# 1_interface.net
KiCad netlist of a schematic drawn in Altium Designer
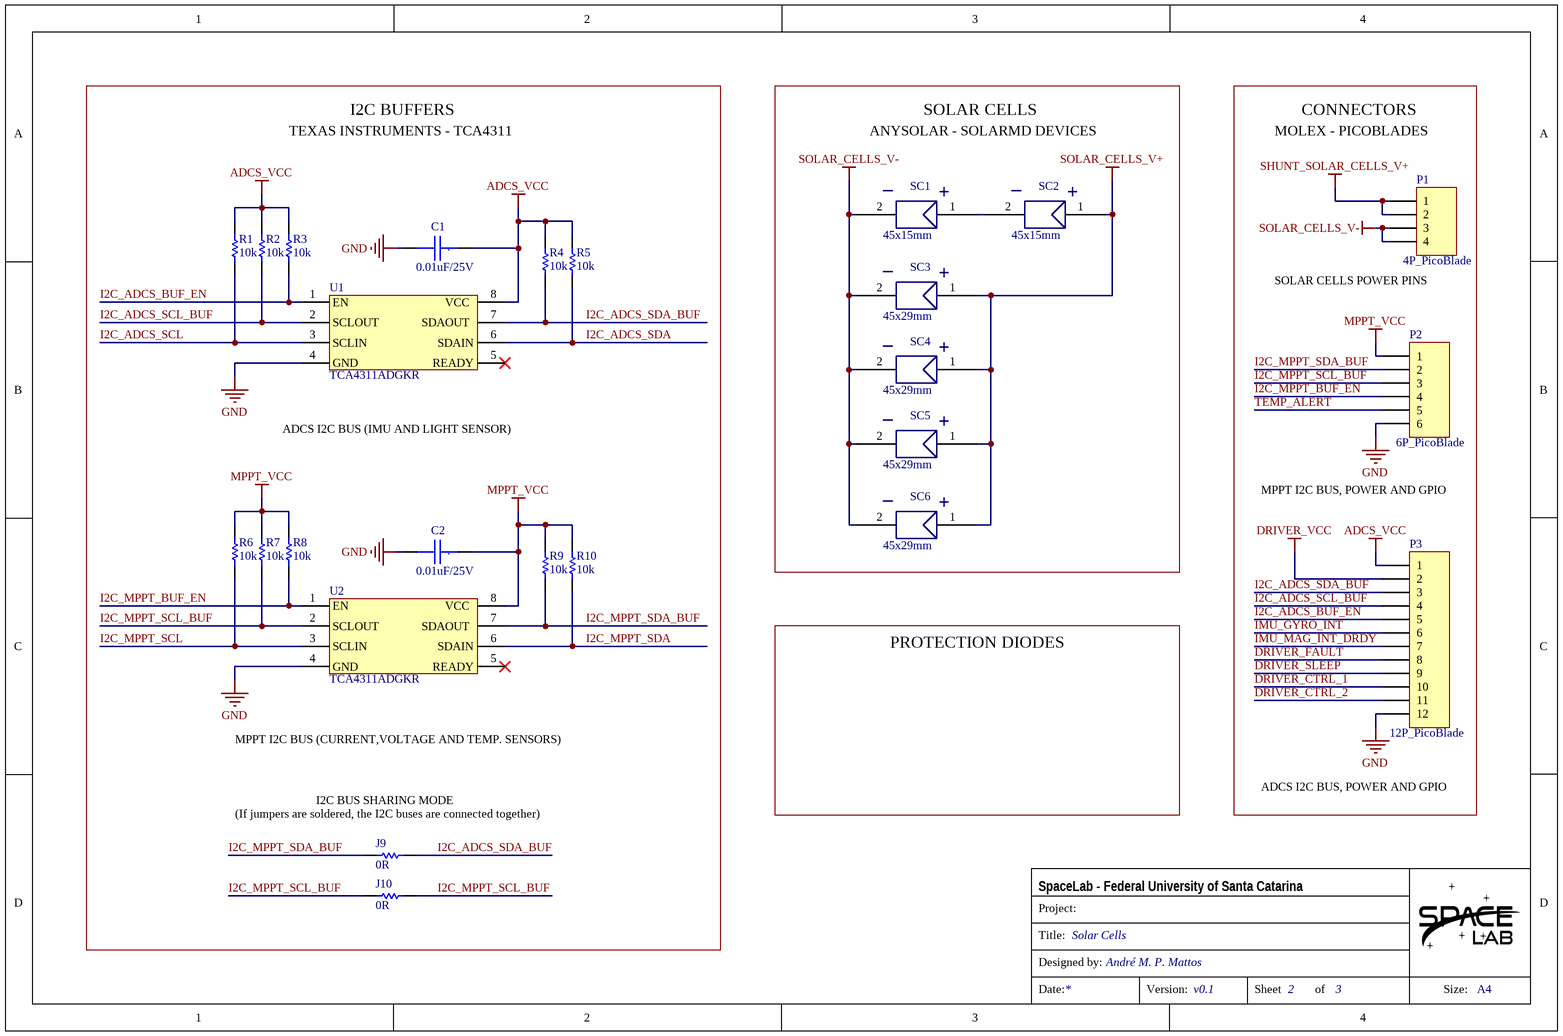
[diagram p0: 1_interface.schdoc]

(export (version "E")
  (design (tool "Eeschema 10.0.6"))
  (components
    (comp (ref "C1")
      (value "0.01uF/25V")
      (footprint "CC0805")
      (description "CAP CER 0.01uF 25V 10% X7R 0805")
      (fields (field (name "PARTNUMBER") "CL21B103KAANNNC"))
      (libsource (lib "schematics_library_legacy") (part "Cap_Cer_X7R_0.01uF_50V_0805"))
    )
    (comp (ref "C2")
      (value "0.01uF/25V")
      (footprint "CC0805")
      (description "CAP CER 0.01uF 25V 10% X7R 0805")
      (fields (field (name "PARTNUMBER") "CL21B103KAANNNC"))
      (libsource (lib "schematics_library_legacy") (part "Cap_Cer_X7R_0.01uF_50V_0805"))
    )
    (comp (ref "J9")
      (value "0R")
      (footprint "0805")
      (description "RES 0R OHM 1/16W JUMPER 0805")
      (fields (field (name "PARTNUMBER") "CRCW08050000Z0EA"))
      (libsource (lib "schematics_library_legacy") (part "R0R_JUMPER_1/16W_0805"))
    )
    (comp (ref "J10")
      (value "0R")
      (footprint "0805")
      (description "RES 0R OHM 1/16W JUMPER 0805")
      (fields (field (name "PARTNUMBER") "CRCW08050000Z0EA"))
      (libsource (lib "schematics_library_legacy") (part "R0R_JUMPER_1/16W_0805"))
    )
    (comp (ref "P1")
      (value "4P_PicoBlade")
      (footprint "HDR4 PicoBlade")
      (description "Header, 4-Pin")
      (fields
        (field (name "PARTNUMBER") "53398-0471")
        (field (name "MANUFACTURER") "Molex")
        (field (name "PUBLISHER") "Altium Limited")
      )
      (libsource (lib "schematics_library_legacy") (part "Header 4_PicoBlade"))
    )
    (comp (ref "P2")
      (value "6P_PicoBlade")
      (footprint "HDR6 PicoBlade")
      (description "Header, 6-Pin, Right Angle")
      (fields (field (name "PARTNUMBER") "53398-0671") (field (name "PUBLISHER") "Altium Limited"))
      (libsource (lib "schematics_library_legacy") (part "Header 6H_PicoBlade"))
    )
    (comp (ref "P3")
      (value "12P_PicoBlade")
      (footprint "HDR12 PicoBlade - duplicate")
      (description "Header, 12-Pin")
      (fields (field (name "PARTNUMBER") "53398-1271") (field (name "PUBLISHER") "Altium Limited"))
      (libsource (lib "schematics_library_legacy") (part "Header 12_PicoBlade"))
    )
    (comp (ref "R1")
      (value "10k")
      (footprint "0805")
      (description "RES 10K OHM 1/8W 1%  0805")
      (fields (field (name "PARTNUMBER") "CRCW080510K0FKEA"))
      (libsource (lib "schematics_library_legacy") (part "R10k_1%_1/8W_0805"))
    )
    (comp (ref "R2")
      (value "10k")
      (footprint "0805")
      (description "RES 10K OHM 1/8W 1%  0805")
      (fields (field (name "PARTNUMBER") "CRCW080510K0FKEA"))
      (libsource (lib "schematics_library_legacy") (part "R10k_1%_1/8W_0805"))
    )
    (comp (ref "R3")
      (value "10k")
      (footprint "0805")
      (description "RES 10K OHM 1/8W 1%  0805")
      (fields (field (name "PARTNUMBER") "CRCW080510K0FKEA"))
      (libsource (lib "schematics_library_legacy") (part "R10k_1%_1/8W_0805"))
    )
    (comp (ref "R4")
      (value "10k")
      (footprint "0805")
      (description "RES 10K OHM 1/8W 1%  0805")
      (fields (field (name "PARTNUMBER") "CRCW080510K0FKEA"))
      (libsource (lib "schematics_library_legacy") (part "R10k_1%_1/8W_0805"))
    )
    (comp (ref "R5")
      (value "10k")
      (footprint "0805")
      (description "RES 10K OHM 1/8W 1%  0805")
      (fields (field (name "PARTNUMBER") "CRCW080510K0FKEA"))
      (libsource (lib "schematics_library_legacy") (part "R10k_1%_1/8W_0805"))
    )
    (comp (ref "R6")
      (value "10k")
      (footprint "0805")
      (description "RES 10K OHM 1/8W 1%  0805")
      (fields (field (name "PARTNUMBER") "CRCW080510K0FKEA"))
      (libsource (lib "schematics_library_legacy") (part "R10k_1%_1/8W_0805"))
    )
    (comp (ref "R7")
      (value "10k")
      (footprint "0805")
      (description "RES 10K OHM 1/8W 1%  0805")
      (fields (field (name "PARTNUMBER") "CRCW080510K0FKEA"))
      (libsource (lib "schematics_library_legacy") (part "R10k_1%_1/8W_0805"))
    )
    (comp (ref "R8")
      (value "10k")
      (footprint "0805")
      (description "RES 10K OHM 1/8W 1%  0805")
      (fields (field (name "PARTNUMBER") "CRCW080510K0FKEA"))
      (libsource (lib "schematics_library_legacy") (part "R10k_1%_1/8W_0805"))
    )
    (comp (ref "R9")
      (value "10k")
      (footprint "0805")
      (description "RES 10K OHM 1/8W 1%  0805")
      (fields (field (name "PARTNUMBER") "CRCW080510K0FKEA"))
      (libsource (lib "schematics_library_legacy") (part "R10k_1%_1/8W_0805"))
    )
    (comp (ref "R10")
      (value "10k")
      (footprint "0805")
      (description "RES 10K OHM 1/8W 1%  0805")
      (fields (field (name "PARTNUMBER") "CRCW080510K0FKEA"))
      (libsource (lib "schematics_library_legacy") (part "R10k_1%_1/8W_0805"))
    )
    (comp (ref "SC1")
      (value "SC")
      (footprint "45x15mm_cell")
      (description "sm141k04lv")
      (fields (field (name "SIZE") "45x15mm"))
      (libsource (lib "schematics_library_legacy") (part "solar_cell_sm141k04lv"))
    )
    (comp (ref "SC2")
      (value "SC")
      (footprint "45x15mm_cell")
      (description "sm141k04lv")
      (fields (field (name "SIZE") "45x15mm"))
      (libsource (lib "schematics_library_legacy") (part "solar_cell_sm141k04lv"))
    )
    (comp (ref "SC3")
      (value "SC")
      (footprint "45x29mm_cell")
      (description "sm141k08lv")
      (fields (field (name "SIZE") "45x29mm"))
      (libsource (lib "schematics_library_legacy") (part "solar_cell_sm141k08lv"))
    )
    (comp (ref "SC4")
      (value "SC")
      (footprint "45x29mm_cell")
      (description "sm141k08lv")
      (fields (field (name "SIZE") "45x29mm"))
      (libsource (lib "schematics_library_legacy") (part "solar_cell_sm141k08lv"))
    )
    (comp (ref "SC5")
      (value "SC")
      (footprint "45x29mm_cell")
      (description "sm141k08lv")
      (fields (field (name "SIZE") "45x29mm"))
      (libsource (lib "schematics_library_legacy") (part "solar_cell_sm141k08lv"))
    )
    (comp (ref "SC6")
      (value "SC")
      (footprint "45x29mm_cell")
      (description "sm141k08lv")
      (fields (field (name "SIZE") "45x29mm"))
      (libsource (lib "schematics_library_legacy") (part "solar_cell_sm141k08lv"))
    )
    (comp (ref "U1")
      (value "TCA4311ADGKR")
      (footprint "DGK8")
      (description "IC SIGNAL BUFFER I2C VSSOP-8")
      (libsource (lib "schematics_library_legacy") (part "TCA4311ADGKR"))
    )
    (comp (ref "U2")
      (value "TCA4311ADGKR")
      (footprint "DGK8")
      (description "IC SIGNAL BUFFER I2C VSSOP-8")
      (libsource (lib "schematics_library_legacy") (part "TCA4311ADGKR"))
    )
  )
  (nets
    (net (code "1") (name "/DRIVER_CTRL_1") (class "Default")
      (node (ref "P3") (pin "10") (pinfunction "10_10") (pintype "passive"))
    )
    (net (code "2") (name "/DRIVER_CTRL_2") (class "Default")
      (node (ref "P3") (pin "11") (pinfunction "11_11") (pintype "passive"))
    )
    (net (code "3") (name "/DRIVER_FAULT") (class "Default")
      (node (ref "P3") (pin "8") (pinfunction "8_8") (pintype "passive"))
    )
    (net (code "4") (name "/DRIVER_SLEEP") (class "Default")
      (node (ref "P3") (pin "9") (pinfunction "9_9") (pintype "passive"))
    )
    (net (code "5") (name "/I2C_ADCS_BUF_EN") (class "Default")
      (node (ref "P3") (pin "5") (pinfunction "5_5") (pintype "passive"))
      (node (ref "R3") (pin "1") (pinfunction "1_1") (pintype "passive"))
      (node (ref "U1") (pin "1") (pinfunction "EN_1") (pintype "passive"))
    )
    (net (code "6") (name "/I2C_ADCS_SCL") (class "Default")
      (node (ref "R1") (pin "1") (pinfunction "1_1") (pintype "passive"))
      (node (ref "U1") (pin "3") (pinfunction "SCLIN_3") (pintype "passive"))
    )
    (net (code "7") (name "/I2C_ADCS_SCL_BUF") (class "Default")
      (node (ref "P3") (pin "4") (pinfunction "4_4") (pintype "passive"))
      (node (ref "R2") (pin "1") (pinfunction "1_1") (pintype "passive"))
      (node (ref "U1") (pin "2") (pinfunction "SCLOUT_2") (pintype "passive"))
    )
    (net (code "8") (name "/I2C_ADCS_SDA") (class "Default")
      (node (ref "R5") (pin "1") (pinfunction "1_1") (pintype "passive"))
      (node (ref "U1") (pin "6") (pinfunction "SDAIN_6") (pintype "passive"))
    )
    (net (code "9") (name "/I2C_ADCS_SDA_BUF") (class "Default")
      (node (ref "J9") (pin "1") (pinfunction "1_1") (pintype "passive"))
      (node (ref "P3") (pin "3") (pinfunction "3_3") (pintype "passive"))
      (node (ref "R4") (pin "1") (pinfunction "1_1") (pintype "passive"))
      (node (ref "U1") (pin "7") (pinfunction "SDAOUT_7") (pintype "passive"))
    )
    (net (code "10") (name "/I2C_MPPT_BUF_EN") (class "Default")
      (node (ref "P2") (pin "4") (pinfunction "4_4") (pintype "passive"))
      (node (ref "R8") (pin "1") (pinfunction "1_1") (pintype "passive"))
      (node (ref "U2") (pin "1") (pinfunction "EN_1") (pintype "passive"))
    )
    (net (code "11") (name "/I2C_MPPT_SCL") (class "Default")
      (node (ref "R6") (pin "1") (pinfunction "1_1") (pintype "passive"))
      (node (ref "U2") (pin "3") (pinfunction "SCLIN_3") (pintype "passive"))
    )
    (net (code "12") (name "/I2C_MPPT_SCL_BUF") (class "Default")
      (node (ref "J10") (pin "1") (pinfunction "1_1") (pintype "passive"))
      (node (ref "J10") (pin "2") (pinfunction "2_2") (pintype "passive"))
      (node (ref "P2") (pin "3") (pinfunction "3_3") (pintype "passive"))
      (node (ref "R7") (pin "1") (pinfunction "1_1") (pintype "passive"))
      (node (ref "U2") (pin "2") (pinfunction "SCLOUT_2") (pintype "passive"))
    )
    (net (code "13") (name "/I2C_MPPT_SDA") (class "Default")
      (node (ref "R10") (pin "1") (pinfunction "1_1") (pintype "passive"))
      (node (ref "U2") (pin "6") (pinfunction "SDAIN_6") (pintype "passive"))
    )
    (net (code "14") (name "/I2C_MPPT_SDA_BUF") (class "Default")
      (node (ref "J9") (pin "2") (pinfunction "2_2") (pintype "passive"))
      (node (ref "P2") (pin "2") (pinfunction "2_2") (pintype "passive"))
      (node (ref "R9") (pin "1") (pinfunction "1_1") (pintype "passive"))
      (node (ref "U2") (pin "7") (pinfunction "SDAOUT_7") (pintype "passive"))
    )
    (net (code "15") (name "/IMU_GYRO_INT") (class "Default")
      (node (ref "P3") (pin "6") (pinfunction "6_6") (pintype "passive"))
    )
    (net (code "16") (name "/IMU_MAG_INT_DRDY") (class "Default")
      (node (ref "P3") (pin "7") (pinfunction "7_7") (pintype "passive"))
    )
    (net (code "17") (name "/TEMP_ALERT") (class "Default")
      (node (ref "P2") (pin "5") (pinfunction "5_5") (pintype "passive"))
    )
    (net (code "18") (name "ADCS_VCC") (class "Default")
      (node (ref "C1") (pin "1") (pinfunction "1_1") (pintype "passive"))
      (node (ref "P3") (pin "1") (pinfunction "1_1") (pintype "passive"))
      (node (ref "R1") (pin "2") (pinfunction "2_2") (pintype "passive"))
      (node (ref "R2") (pin "2") (pinfunction "2_2") (pintype "passive"))
      (node (ref "R3") (pin "2") (pinfunction "2_2") (pintype "passive"))
      (node (ref "R4") (pin "2") (pinfunction "2_2") (pintype "passive"))
      (node (ref "R5") (pin "2") (pinfunction "2_2") (pintype "passive"))
      (node (ref "U1") (pin "8") (pinfunction "VCC_8") (pintype "power_in"))
    )
    (net (code "19") (name "DRIVER_VCC") (class "Default")
      (node (ref "P3") (pin "2") (pinfunction "2_2") (pintype "passive"))
    )
    (net (code "20") (name "GND") (class "Default")
      (node (ref "C1") (pin "2") (pinfunction "2_2") (pintype "passive"))
      (node (ref "C2") (pin "2") (pinfunction "2_2") (pintype "passive"))
      (node (ref "P2") (pin "6") (pinfunction "6_6") (pintype "passive"))
      (node (ref "P3") (pin "12") (pinfunction "12_12") (pintype "passive"))
      (node (ref "U1") (pin "4") (pinfunction "GND_4") (pintype "passive"))
      (node (ref "U2") (pin "4") (pinfunction "GND_4") (pintype "passive"))
    )
    (net (code "21") (name "MPPT_VCC") (class "Default")
      (node (ref "C2") (pin "1") (pinfunction "1_1") (pintype "passive"))
      (node (ref "P2") (pin "1") (pinfunction "1_1") (pintype "passive"))
      (node (ref "R10") (pin "2") (pinfunction "2_2") (pintype "passive"))
      (node (ref "R6") (pin "2") (pinfunction "2_2") (pintype "passive"))
      (node (ref "R7") (pin "2") (pinfunction "2_2") (pintype "passive"))
      (node (ref "R8") (pin "2") (pinfunction "2_2") (pintype "passive"))
      (node (ref "R9") (pin "2") (pinfunction "2_2") (pintype "passive"))
      (node (ref "U2") (pin "8") (pinfunction "VCC_8") (pintype "power_in"))
    )
    (net (code "22") (name "Net-(SC1-V+)") (class "Default")
      (node (ref "SC1") (pin "1") (pinfunction "V+_1") (pintype "power_in"))
      (node (ref "SC2") (pin "2") (pinfunction "V-_2") (pintype "power_in"))
    )
    (net (code "23") (name "SHUNT_SOLAR_CELLS_V+") (class "Default")
      (node (ref "P1") (pin "1") (pinfunction "1_1") (pintype "passive"))
      (node (ref "P1") (pin "2") (pinfunction "2_2") (pintype "passive"))
    )
    (net (code "24") (name "SOLAR_CELLS_V+") (class "Default")
      (node (ref "SC2") (pin "1") (pinfunction "V+_1") (pintype "power_in"))
      (node (ref "SC3") (pin "1") (pinfunction "V+_1") (pintype "power_in"))
      (node (ref "SC4") (pin "1") (pinfunction "V+_1") (pintype "power_in"))
      (node (ref "SC5") (pin "1") (pinfunction "V+_1") (pintype "power_in"))
      (node (ref "SC6") (pin "1") (pinfunction "V+_1") (pintype "power_in"))
    )
    (net (code "25") (name "SOLAR_CELLS_V-") (class "Default")
      (node (ref "P1") (pin "3") (pinfunction "3_3") (pintype "passive"))
      (node (ref "P1") (pin "4") (pinfunction "4_4") (pintype "passive"))
      (node (ref "SC1") (pin "2") (pinfunction "V-_2") (pintype "power_in"))
      (node (ref "SC3") (pin "2") (pinfunction "V-_2") (pintype "power_in"))
      (node (ref "SC4") (pin "2") (pinfunction "V-_2") (pintype "power_in"))
      (node (ref "SC5") (pin "2") (pinfunction "V-_2") (pintype "power_in"))
      (node (ref "SC6") (pin "2") (pinfunction "V-_2") (pintype "power_in"))
    )
    (net (code "26") (name "unconnected-(U1-READY-Pad5)") (class "Default")
      (node (ref "U1") (pin "5") (pinfunction "READY_5") (pintype "passive+no_connect"))
    )
    (net (code "27") (name "unconnected-(U2-READY-Pad5)") (class "Default")
      (node (ref "U2") (pin "5") (pinfunction "READY_5") (pintype "passive+no_connect"))
    )
  )
)
